# owl-digital-2.net
KiCad netlist of a schematic drawn in EAGLE
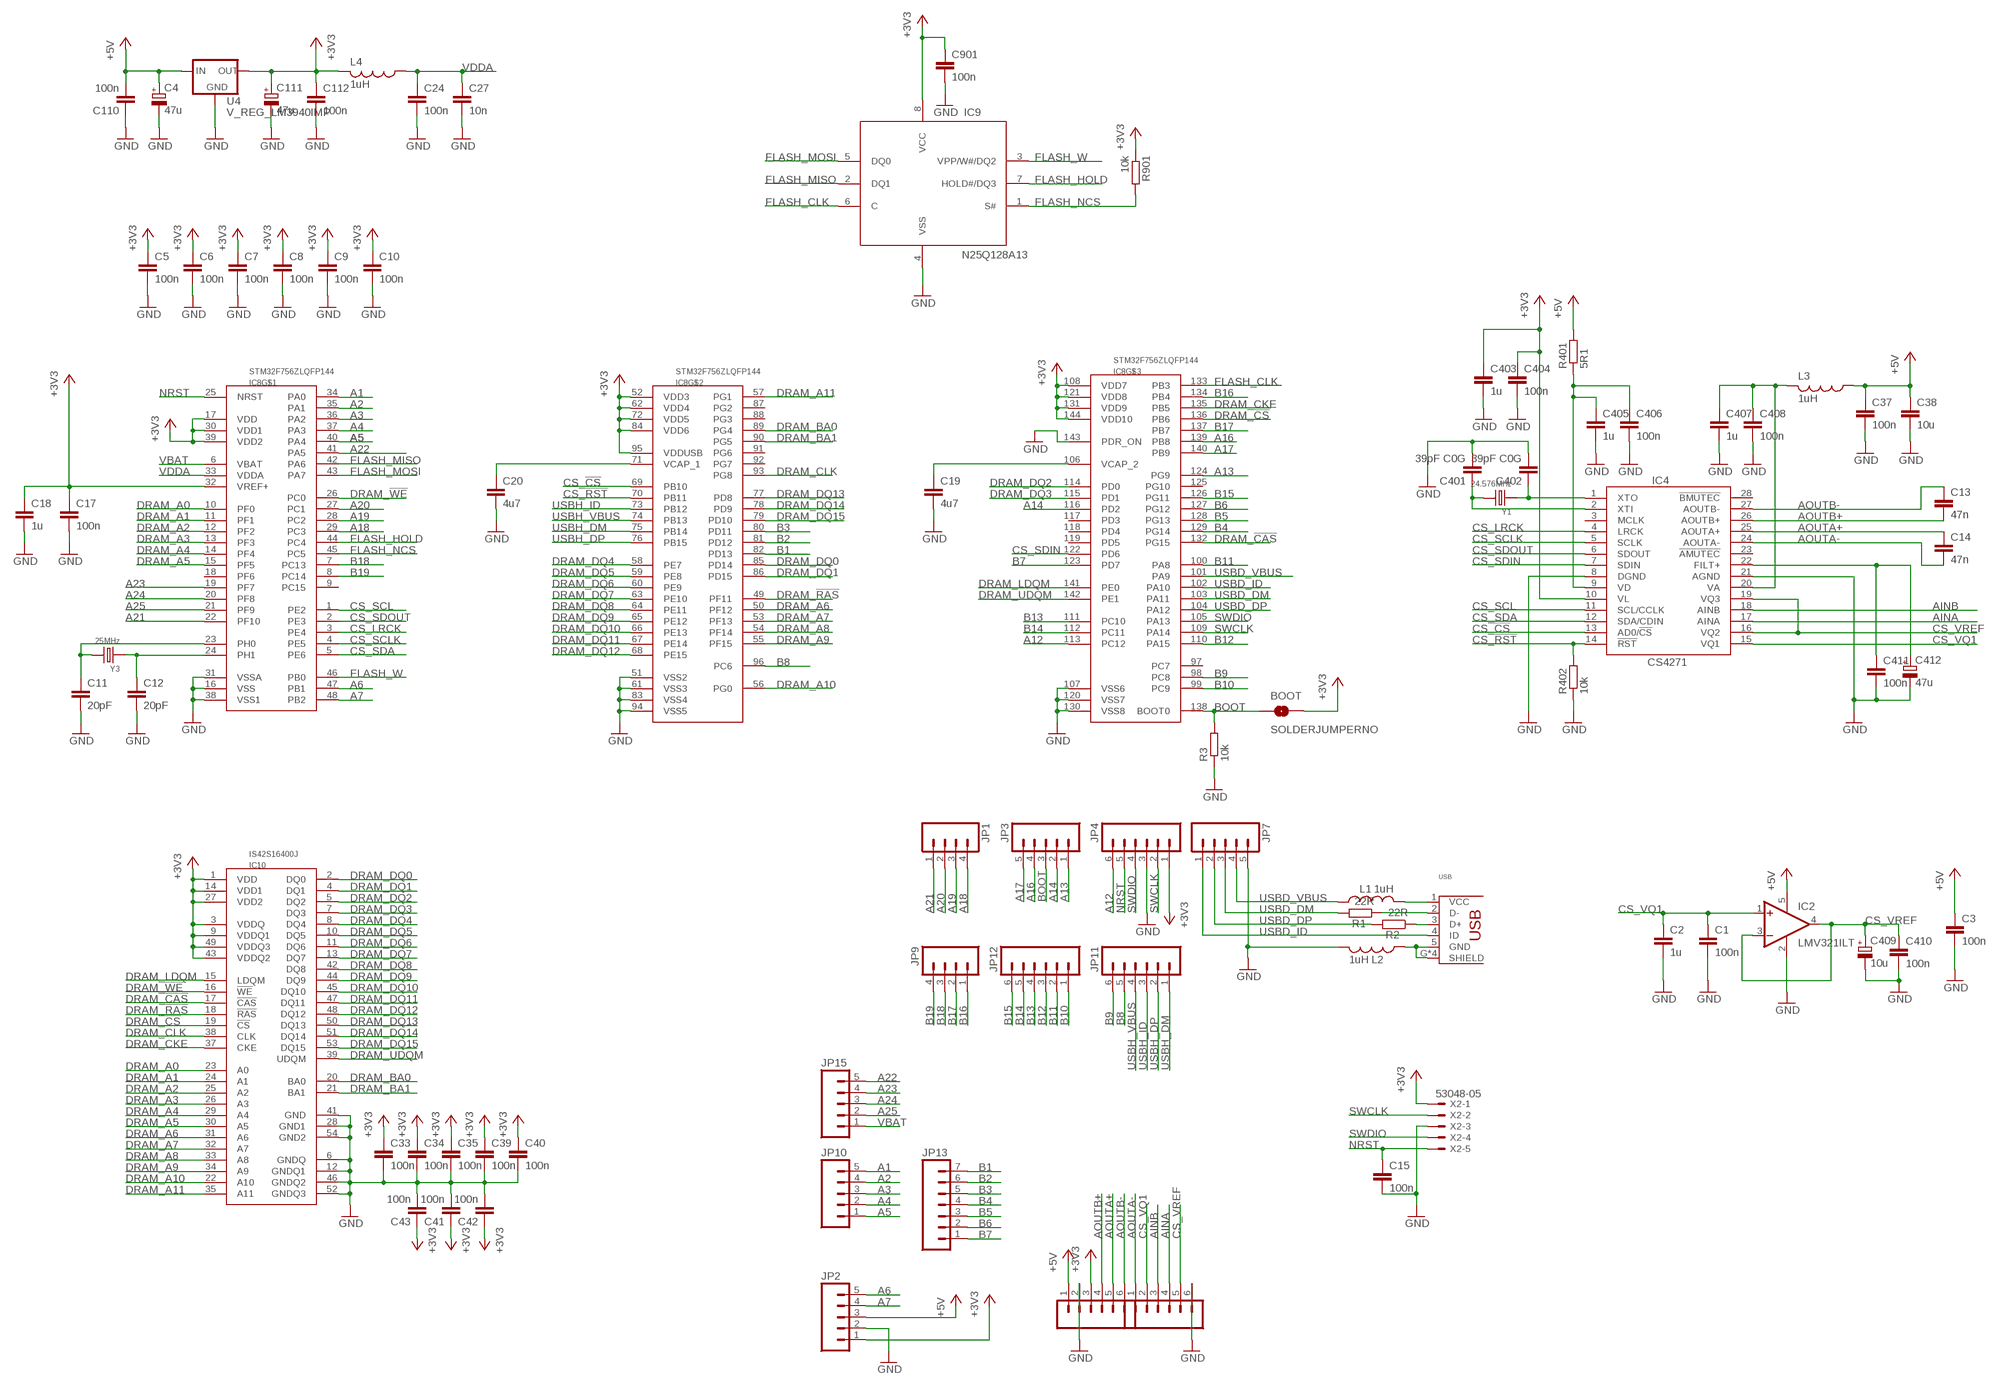
[diagram p0: schematic, sheet 1]

(export (version "E")
  (design (tool "Eeschema 10.0.6"))
  (components
    (comp (ref "BOOT")
      (value "SOLDERJUMPERNO")
      (footprint "eagle-import:SJ_2S-NO")
      (libsource (lib "eagle-import") (part "SOLDERJUMPERNO"))
    )
    (comp (ref "C1")
      (value "100n")
      (footprint "eagle-import:C0603")
      (libsource (lib "eagle-import") (part "C-EUC0603"))
    )
    (comp (ref "C2")
      (value "1u")
      (footprint "eagle-import:C0603")
      (libsource (lib "eagle-import") (part "C-EUC0603"))
    )
    (comp (ref "C3")
      (value "100n")
      (footprint "eagle-import:C0603")
      (libsource (lib "eagle-import") (part "C-EUC0603"))
    )
    (comp (ref "C4")
      (value "47u")
      (footprint "eagle-import:CPOL-5")
      (libsource (lib "eagle-import") (part "CPOL-EU153CLV-0505"))
    )
    (comp (ref "C5")
      (value "100n")
      (footprint "eagle-import:C0603")
      (libsource (lib "eagle-import") (part "C-EUC0603"))
    )
    (comp (ref "C6")
      (value "100n")
      (footprint "eagle-import:C0603")
      (libsource (lib "eagle-import") (part "C-EUC0603"))
    )
    (comp (ref "C7")
      (value "100n")
      (footprint "eagle-import:C0603")
      (libsource (lib "eagle-import") (part "C-EUC0603"))
    )
    (comp (ref "C8")
      (value "100n")
      (footprint "eagle-import:C0603")
      (libsource (lib "eagle-import") (part "C-EUC0603"))
    )
    (comp (ref "C9")
      (value "100n")
      (footprint "eagle-import:C0603")
      (libsource (lib "eagle-import") (part "C-EUC0603"))
    )
    (comp (ref "C10")
      (value "100n")
      (footprint "eagle-import:C0603")
      (libsource (lib "eagle-import") (part "C-EUC0603"))
    )
    (comp (ref "C11")
      (value "20pF")
      (footprint "eagle-import:C0603")
      (libsource (lib "eagle-import") (part "C-EUC0603"))
    )
    (comp (ref "C12")
      (value "20pF")
      (footprint "eagle-import:C0603")
      (libsource (lib "eagle-import") (part "C-EUC0603"))
    )
    (comp (ref "C13")
      (value "47n")
      (footprint "eagle-import:C0603")
      (libsource (lib "eagle-import") (part "C-EUC0603"))
    )
    (comp (ref "C14")
      (value "47n")
      (footprint "eagle-import:C0603")
      (libsource (lib "eagle-import") (part "C-EUC0603"))
    )
    (comp (ref "C15")
      (value "100n")
      (footprint "eagle-import:C0603")
      (libsource (lib "eagle-import") (part "C-EUC0603"))
    )
    (comp (ref "C17")
      (value "100n")
      (footprint "eagle-import:C0603")
      (libsource (lib "eagle-import") (part "C-EUC0603"))
    )
    (comp (ref "C18")
      (value "1u")
      (footprint "eagle-import:C0603")
      (libsource (lib "eagle-import") (part "C-EUC0603"))
    )
    (comp (ref "C19")
      (value "4u7")
      (footprint "eagle-import:C0603")
      (libsource (lib "eagle-import") (part "C-EUC0603"))
    )
    (comp (ref "C20")
      (value "4u7")
      (footprint "eagle-import:C0603")
      (libsource (lib "eagle-import") (part "C-EUC0603"))
    )
    (comp (ref "C24")
      (value "100n")
      (footprint "eagle-import:C0603")
      (libsource (lib "eagle-import") (part "C-EUC0603"))
    )
    (comp (ref "C27")
      (value "10n")
      (footprint "eagle-import:C0603")
      (libsource (lib "eagle-import") (part "C-EUC0603"))
    )
    (comp (ref "C33")
      (value "100n")
      (footprint "eagle-import:C0603")
      (libsource (lib "eagle-import") (part "C-EUC0603"))
    )
    (comp (ref "C34")
      (value "100n")
      (footprint "eagle-import:C0603")
      (libsource (lib "eagle-import") (part "C-EUC0603"))
    )
    (comp (ref "C35")
      (value "100n")
      (footprint "eagle-import:C0603")
      (libsource (lib "eagle-import") (part "C-EUC0603"))
    )
    (comp (ref "C37")
      (value "100n")
      (footprint "eagle-import:C0603")
      (libsource (lib "eagle-import") (part "C-EUC0603"))
    )
    (comp (ref "C38")
      (value "10u")
      (footprint "eagle-import:C1206")
      (libsource (lib "eagle-import") (part "C-EUC1206"))
    )
    (comp (ref "C39")
      (value "100n")
      (footprint "eagle-import:C0603")
      (libsource (lib "eagle-import") (part "C-EUC0603"))
    )
    (comp (ref "C40")
      (value "100n")
      (footprint "eagle-import:C0603")
      (libsource (lib "eagle-import") (part "C-EUC0603"))
    )
    (comp (ref "C41")
      (value "100n")
      (footprint "eagle-import:C0603")
      (libsource (lib "eagle-import") (part "C-EUC0603"))
    )
    (comp (ref "C42")
      (value "100n")
      (footprint "eagle-import:C0603")
      (libsource (lib "eagle-import") (part "C-EUC0603"))
    )
    (comp (ref "C43")
      (value "100n")
      (footprint "eagle-import:C0603")
      (libsource (lib "eagle-import") (part "C-EUC0603"))
    )
    (comp (ref "C110")
      (value "100n")
      (footprint "eagle-import:C0603")
      (libsource (lib "eagle-import") (part "C-EUC0603"))
    )
    (comp (ref "C111")
      (value "47u")
      (footprint "eagle-import:CPOL-5")
      (libsource (lib "eagle-import") (part "CPOL-EU153CLV-0505"))
    )
    (comp (ref "C112")
      (value "100n")
      (footprint "eagle-import:C0603")
      (libsource (lib "eagle-import") (part "C-EUC0603"))
    )
    (comp (ref "C401")
      (value "39pF C0G")
      (footprint "eagle-import:C0603")
      (libsource (lib "eagle-import") (part "C-EUC0603"))
    )
    (comp (ref "C402")
      (value "39pF C0G")
      (footprint "eagle-import:C0603")
      (libsource (lib "eagle-import") (part "C-EUC0603"))
    )
    (comp (ref "C403")
      (value "1u")
      (footprint "eagle-import:C0603")
      (libsource (lib "eagle-import") (part "C-EUC0603"))
    )
    (comp (ref "C404")
      (value "100n")
      (footprint "eagle-import:C0603")
      (libsource (lib "eagle-import") (part "C-EUC0603"))
    )
    (comp (ref "C405")
      (value "1u")
      (footprint "eagle-import:C0603")
      (libsource (lib "eagle-import") (part "C-EUC0603"))
    )
    (comp (ref "C406")
      (value "100n")
      (footprint "eagle-import:C0603")
      (libsource (lib "eagle-import") (part "C-EUC0603"))
    )
    (comp (ref "C407")
      (value "1u")
      (footprint "eagle-import:C0603")
      (libsource (lib "eagle-import") (part "C-EUC0603"))
    )
    (comp (ref "C408")
      (value "100n")
      (footprint "eagle-import:C0603")
      (libsource (lib "eagle-import") (part "C-EUC0603"))
    )
    (comp (ref "C409")
      (value "10u")
      (footprint "eagle-import:CPOL-5")
      (libsource (lib "eagle-import") (part "CPOL-EU153CLV-0505"))
    )
    (comp (ref "C410")
      (value "100n")
      (footprint "eagle-import:C0603")
      (libsource (lib "eagle-import") (part "C-EUC0603"))
    )
    (comp (ref "C411")
      (value "100n")
      (footprint "eagle-import:C0603")
      (libsource (lib "eagle-import") (part "C-EUC0603"))
    )
    (comp (ref "C412")
      (value "47u")
      (footprint "eagle-import:CPOL-5")
      (libsource (lib "eagle-import") (part "CPOL-EU153CLV-0505"))
    )
    (comp (ref "C901")
      (value "100n")
      (footprint "eagle-import:C0603")
      (libsource (lib "eagle-import") (part "C-EUC0603"))
    )
    (comp (ref "IC2")
      (value "LMV321ILT")
      (footprint "eagle-import:SOT23-5")
      (libsource (lib "eagle-import") (part "LM321?MF"))
    )
    (comp (ref "IC4")
      (value "CS4271")
      (footprint "eagle-import:TSSOP28-0.65-9.7X4.4MM")
      (libsource (lib "eagle-import") (part "CS4271"))
    )
    (comp (ref "IC8")
      (value "STM32F756ZLQFP144")
      (footprint "eagle-import:QFP50P2200X2200X160-144N")
      (fields (field (name "OC_FARNELL") "2484975"))
      (libsource (lib "eagle-import") (part "STM32F756ZLQFP144"))
    )
    (comp (ref "IC9")
      (value "N25Q128A13")
      (footprint "eagle-import:SO8W")
      (libsource (lib "eagle-import") (part "N25Q128A13"))
    )
    (comp (ref "IC10")
      (value "IS42S16400J")
      (footprint "eagle-import:TSOP54-400")
      (libsource (lib "eagle-import") (part "IS42S16400J"))
    )
    (comp (ref "JP1")
      (value "M04PTH")
      (footprint "eagle-import:1X04")
      (libsource (lib "eagle-import") (part "M04PTH"))
    )
    (comp (ref "JP2")
      (value "M05PTH")
      (footprint "eagle-import:1X05")
      (libsource (lib "eagle-import") (part "M05PTH"))
    )
    (comp (ref "JP3")
      (value "M05PTH")
      (footprint "eagle-import:1X05")
      (libsource (lib "eagle-import") (part "M05PTH"))
    )
    (comp (ref "JP4")
      (value "M06SIP")
      (footprint "eagle-import:1X06")
      (libsource (lib "eagle-import") (part "M06SIP"))
    )
    (comp (ref "JP5")
      (value "M06SIP")
      (footprint "eagle-import:1X06")
      (libsource (lib "eagle-import") (part "M06SIP"))
    )
    (comp (ref "JP6")
      (value "M06SIP")
      (footprint "eagle-import:1X06")
      (libsource (lib "eagle-import") (part "M06SIP"))
    )
    (comp (ref "JP7")
      (value "M05PTH")
      (footprint "eagle-import:1X05")
      (libsource (lib "eagle-import") (part "M05PTH"))
    )
    (comp (ref "JP9")
      (value "M04PTH")
      (footprint "eagle-import:1X04")
      (libsource (lib "eagle-import") (part "M04PTH"))
    )
    (comp (ref "JP10")
      (value "M05PTH")
      (footprint "eagle-import:1X05")
      (libsource (lib "eagle-import") (part "M05PTH"))
    )
    (comp (ref "JP11")
      (value "M06SIP")
      (footprint "eagle-import:1X06")
      (libsource (lib "eagle-import") (part "M06SIP"))
    )
    (comp (ref "JP12")
      (value "M06SIP")
      (footprint "eagle-import:1X06")
      (libsource (lib "eagle-import") (part "M06SIP"))
    )
    (comp (ref "JP13")
      (value "M07")
      (footprint "eagle-import:1X07")
      (libsource (lib "eagle-import") (part "M07"))
    )
    (comp (ref "JP15")
      (value "M05PTH")
      (footprint "eagle-import:1X05")
      (libsource (lib "eagle-import") (part "M05PTH"))
    )
    (comp (ref "L1")
      (value "1uH")
      (footprint "eagle-import:0603")
      (libsource (lib "eagle-import") (part "INDUCTOR"))
    )
    (comp (ref "L2")
      (value "1uH")
      (footprint "eagle-import:0603")
      (libsource (lib "eagle-import") (part "INDUCTOR"))
    )
    (comp (ref "L3")
      (value "1uH")
      (footprint "eagle-import:0603")
      (libsource (lib "eagle-import") (part "INDUCTOR"))
    )
    (comp (ref "L4")
      (value "1uH")
      (footprint "eagle-import:0603")
      (libsource (lib "eagle-import") (part "INDUCTOR"))
    )
    (comp (ref "R1")
      (value "22R")
      (footprint "eagle-import:0603")
      (libsource (lib "eagle-import") (part "R-EU_0603"))
    )
    (comp (ref "R2")
      (value "22R")
      (footprint "eagle-import:0603")
      (libsource (lib "eagle-import") (part "R-EU_0603"))
    )
    (comp (ref "R3")
      (value "10k")
      (footprint "eagle-import:0603")
      (libsource (lib "eagle-import") (part "R-EU_0603"))
    )
    (comp (ref "R401")
      (value "5R1")
      (footprint "eagle-import:0603")
      (libsource (lib "eagle-import") (part "R-EU_0603"))
    )
    (comp (ref "R402")
      (value "10k")
      (footprint "eagle-import:0603")
      (libsource (lib "eagle-import") (part "R-EU_0603"))
    )
    (comp (ref "R901")
      (value "10k")
      (footprint "eagle-import:0603")
      (libsource (lib "eagle-import") (part "R-EU_0603"))
    )
    (comp (ref "U4")
      (value "V_REG_LM3940IMP")
      (footprint "eagle-import:SOT223")
      (libsource (lib "eagle-import") (part "V_REG_LM3940IMP"))
    )
    (comp (ref "USB")
      (value "USB_HRS_ZX62-B-5PA(11)MICRO.B")
      (footprint "eagle-import:HRS_ZX62RD-AB-5P8")
      (libsource (lib "eagle-import") (part "USB_HRS_ZX62-B-5PA(11)MICRO.B"))
    )
    (comp (ref "X2")
      (value "53048-05")
      (footprint "eagle-import:53048-05")
      (fields (field (name "MF") "MOLEX") (field (name "MPN") "53048-0510"))
      (libsource (lib "eagle-import") (part "53?-05048"))
    )
    (comp (ref "Y1")
      (value "24.576MHz")
      (footprint "eagle-import:X2-SMD-5.0X3.2X1.3MM")
      (fields (field (name "MPN") "5032/2P"))
      (libsource (lib "eagle-import") (part "SMD-CRYSTAL-8MHZ-20PF-20PPM(2P-5.0X3.2MM)"))
    )
    (comp (ref "Y3")
      (value "25MHz")
      (footprint "eagle-import:X2-SMD-5.0X3.2X1.3MM")
      (fields (field (name "MPN") "5032/2P"))
      (libsource (lib "eagle-import") (part "SMD-CRYSTAL-8MHZ-20PF-20PPM(2P-5.0X3.2MM)"))
    )
  )
  (nets
    (net (code "1") (name "+3V3") (class "Default")
      (node (ref "BOOT") (pin "2") (pinfunction "2_2") (pintype "passive"))
      (node (ref "C10") (pin "1") (pinfunction "1_1") (pintype "passive"))
      (node (ref "C111") (pin "+") (pinfunction "+_+") (pintype "passive"))
      (node (ref "C112") (pin "1") (pinfunction "1_1") (pintype "passive"))
      (node (ref "C17") (pin "1") (pinfunction "1_1") (pintype "passive"))
      (node (ref "C18") (pin "1") (pinfunction "1_1") (pintype "passive"))
      (node (ref "C33") (pin "1") (pinfunction "1_1") (pintype "passive"))
      (node (ref "C34") (pin "1") (pinfunction "1_1") (pintype "passive"))
      (node (ref "C35") (pin "1") (pinfunction "1_1") (pintype "passive"))
      (node (ref "C39") (pin "1") (pinfunction "1_1") (pintype "passive"))
      (node (ref "C40") (pin "1") (pinfunction "1_1") (pintype "passive"))
      (node (ref "C403") (pin "1") (pinfunction "1_1") (pintype "passive"))
      (node (ref "C404") (pin "1") (pinfunction "1_1") (pintype "passive"))
      (node (ref "C41") (pin "1") (pinfunction "1_1") (pintype "passive"))
      (node (ref "C42") (pin "1") (pinfunction "1_1") (pintype "passive"))
      (node (ref "C43") (pin "1") (pinfunction "1_1") (pintype "passive"))
      (node (ref "C5") (pin "1") (pinfunction "1_1") (pintype "passive"))
      (node (ref "C6") (pin "1") (pinfunction "1_1") (pintype "passive"))
      (node (ref "C7") (pin "1") (pinfunction "1_1") (pintype "passive"))
      (node (ref "C8") (pin "1") (pinfunction "1_1") (pintype "passive"))
      (node (ref "C9") (pin "1") (pinfunction "1_1") (pintype "passive"))
      (node (ref "C901") (pin "1") (pinfunction "1_1") (pintype "passive"))
      (node (ref "IC10") (pin "1") (pinfunction "VDD_1") (pintype "bidirectional"))
      (node (ref "IC10") (pin "14") (pinfunction "VDD1_14") (pintype "bidirectional"))
      (node (ref "IC10") (pin "27") (pinfunction "VDD2_27") (pintype "bidirectional"))
      (node (ref "IC10") (pin "3") (pinfunction "VDDQ_3") (pintype "bidirectional"))
      (node (ref "IC10") (pin "43") (pinfunction "VDDQ2_43") (pintype "bidirectional"))
      (node (ref "IC10") (pin "49") (pinfunction "VDDQ3_49") (pintype "bidirectional"))
      (node (ref "IC10") (pin "9") (pinfunction "VDDQ1_9") (pintype "bidirectional"))
      (node (ref "IC4") (pin "10") (pinfunction "VL_10") (pintype "bidirectional"))
      (node (ref "IC8") (pin "108") (pinfunction "VDD7_108") (pintype "bidirectional"))
      (node (ref "IC8") (pin "121") (pinfunction "VDD8_121") (pintype "bidirectional"))
      (node (ref "IC8") (pin "131") (pinfunction "VDD9_131") (pintype "bidirectional"))
      (node (ref "IC8") (pin "144") (pinfunction "VDD10_144") (pintype "bidirectional"))
      (node (ref "IC8") (pin "17") (pinfunction "VDD_17") (pintype "bidirectional"))
      (node (ref "IC8") (pin "30") (pinfunction "VDD1_30") (pintype "bidirectional"))
      (node (ref "IC8") (pin "32") (pinfunction "VREF+_32") (pintype "bidirectional"))
      (node (ref "IC8") (pin "39") (pinfunction "VDD2_39") (pintype "bidirectional"))
      (node (ref "IC8") (pin "52") (pinfunction "VDD3_52") (pintype "bidirectional"))
      (node (ref "IC8") (pin "62") (pinfunction "VDD4_62") (pintype "bidirectional"))
      (node (ref "IC8") (pin "72") (pinfunction "VDD5_72") (pintype "bidirectional"))
      (node (ref "IC8") (pin "84") (pinfunction "VDD6_84") (pintype "bidirectional"))
      (node (ref "IC8") (pin "95") (pinfunction "VDDUSB_95") (pintype "bidirectional"))
      (node (ref "IC9") (pin "8") (pinfunction "VCC_8") (pintype "bidirectional"))
      (node (ref "JP2") (pin "1") (pinfunction "1_1") (pintype "passive"))
      (node (ref "JP4") (pin "1") (pinfunction "1_1") (pintype "passive"))
      (node (ref "JP5") (pin "3") (pinfunction "3_3") (pintype "passive"))
      (node (ref "L4") (pin "2") (pinfunction "2_2") (pintype "passive"))
      (node (ref "R901") (pin "1") (pinfunction "1_1") (pintype "passive"))
      (node (ref "U4") (pin "3") (pinfunction "OUT_3") (pintype "output"))
      (node (ref "X2") (pin "1") (pinfunction "S_1") (pintype "passive"))
    )
    (net (code "2") (name "+5V") (class "Default")
      (node (ref "C110") (pin "2") (pinfunction "2_2") (pintype "passive"))
      (node (ref "C3") (pin "1") (pinfunction "1_1") (pintype "passive"))
      (node (ref "C37") (pin "1") (pinfunction "1_1") (pintype "passive"))
      (node (ref "C38") (pin "1") (pinfunction "1_1") (pintype "passive"))
      (node (ref "C4") (pin "+") (pinfunction "+_+") (pintype "passive"))
      (node (ref "IC2") (pin "5") (pinfunction "V+_5") (pintype "power_in"))
      (node (ref "JP2") (pin "3") (pinfunction "3_3") (pintype "passive"))
      (node (ref "JP5") (pin "1") (pinfunction "1_1") (pintype "passive"))
      (node (ref "L3") (pin "1") (pinfunction "1_1") (pintype "passive"))
      (node (ref "R401") (pin "2") (pinfunction "2_2") (pintype "passive"))
      (node (ref "U4") (pin "1") (pinfunction "IN_1") (pintype "input"))
    )
    (net (code "3") (name "/A1") (class "Default")
      (node (ref "IC8") (pin "34") (pinfunction "PA0_34") (pintype "bidirectional"))
      (node (ref "JP10") (pin "5") (pinfunction "5_5") (pintype "passive"))
    )
    (net (code "4") (name "/A2") (class "Default")
      (node (ref "IC8") (pin "35") (pinfunction "PA1_35") (pintype "bidirectional"))
      (node (ref "JP10") (pin "4") (pinfunction "4_4") (pintype "passive"))
    )
    (net (code "5") (name "/A3") (class "Default")
      (node (ref "IC8") (pin "36") (pinfunction "PA2_36") (pintype "bidirectional"))
      (node (ref "JP10") (pin "3") (pinfunction "3_3") (pintype "passive"))
    )
    (net (code "6") (name "/A4") (class "Default")
      (node (ref "IC8") (pin "37") (pinfunction "PA3_37") (pintype "bidirectional"))
      (node (ref "JP10") (pin "2") (pinfunction "2_2") (pintype "passive"))
    )
    (net (code "7") (name "/A5") (class "Default")
      (node (ref "IC8") (pin "40") (pinfunction "PA4_40") (pintype "bidirectional"))
      (node (ref "JP10") (pin "1") (pinfunction "1_1") (pintype "passive"))
    )
    (net (code "8") (name "/A6") (class "Default")
      (node (ref "IC8") (pin "47") (pinfunction "PB1_47") (pintype "bidirectional"))
      (node (ref "JP2") (pin "5") (pinfunction "5_5") (pintype "passive"))
    )
    (net (code "9") (name "/A7") (class "Default")
      (node (ref "IC8") (pin "48") (pinfunction "PB2_48") (pintype "bidirectional"))
      (node (ref "JP2") (pin "4") (pinfunction "4_4") (pintype "passive"))
    )
    (net (code "10") (name "/A12") (class "Default")
      (node (ref "IC8") (pin "113") (pinfunction "PC12_113") (pintype "bidirectional"))
      (node (ref "JP4") (pin "6") (pinfunction "6_6") (pintype "passive"))
    )
    (net (code "11") (name "/A13") (class "Default")
      (node (ref "IC8") (pin "124") (pinfunction "PG9_124") (pintype "bidirectional"))
      (node (ref "JP3") (pin "1") (pinfunction "1_1") (pintype "passive"))
    )
    (net (code "12") (name "/A14") (class "Default")
      (node (ref "IC8") (pin "116") (pinfunction "PD2_116") (pintype "bidirectional"))
      (node (ref "JP3") (pin "2") (pinfunction "2_2") (pintype "passive"))
    )
    (net (code "13") (name "/A16") (class "Default")
      (node (ref "IC8") (pin "139") (pinfunction "PB8_139") (pintype "bidirectional"))
      (node (ref "JP3") (pin "4") (pinfunction "4_4") (pintype "passive"))
    )
    (net (code "14") (name "/A17") (class "Default")
      (node (ref "IC8") (pin "140") (pinfunction "PB9_140") (pintype "bidirectional"))
      (node (ref "JP3") (pin "5") (pinfunction "5_5") (pintype "passive"))
    )
    (net (code "15") (name "/A18") (class "Default")
      (node (ref "IC8") (pin "29") (pinfunction "PC3_29") (pintype "bidirectional"))
      (node (ref "JP1") (pin "4") (pinfunction "4_4") (pintype "passive"))
    )
    (net (code "16") (name "/A19") (class "Default")
      (node (ref "IC8") (pin "28") (pinfunction "PC2_28") (pintype "bidirectional"))
      (node (ref "JP1") (pin "3") (pinfunction "3_3") (pintype "passive"))
    )
    (net (code "17") (name "/A20") (class "Default")
      (node (ref "IC8") (pin "27") (pinfunction "PC1_27") (pintype "bidirectional"))
      (node (ref "JP1") (pin "2") (pinfunction "2_2") (pintype "passive"))
    )
    (net (code "18") (name "/A21") (class "Default")
      (node (ref "IC8") (pin "22") (pinfunction "PF10_22") (pintype "bidirectional"))
      (node (ref "JP1") (pin "1") (pinfunction "1_1") (pintype "passive"))
    )
    (net (code "19") (name "/A22") (class "Default")
      (node (ref "IC8") (pin "41") (pinfunction "PA5_41") (pintype "bidirectional"))
      (node (ref "JP15") (pin "5") (pinfunction "5_5") (pintype "passive"))
    )
    (net (code "20") (name "/A23") (class "Default")
      (node (ref "IC8") (pin "19") (pinfunction "PF7_19") (pintype "bidirectional"))
      (node (ref "JP15") (pin "4") (pinfunction "4_4") (pintype "passive"))
    )
    (net (code "21") (name "/A24") (class "Default")
      (node (ref "IC8") (pin "20") (pinfunction "PF8_20") (pintype "bidirectional"))
      (node (ref "JP15") (pin "3") (pinfunction "3_3") (pintype "passive"))
    )
    (net (code "22") (name "/A25") (class "Default")
      (node (ref "IC8") (pin "21") (pinfunction "PF9_21") (pintype "bidirectional"))
      (node (ref "JP15") (pin "2") (pinfunction "2_2") (pintype "passive"))
    )
    (net (code "23") (name "/AINA") (class "Default")
      (node (ref "IC4") (pin "17") (pinfunction "AINA_17") (pintype "bidirectional"))
      (node (ref "JP6") (pin "4") (pinfunction "4_4") (pintype "passive"))
    )
    (net (code "24") (name "/AINB") (class "Default")
      (node (ref "IC4") (pin "18") (pinfunction "AINB_18") (pintype "bidirectional"))
      (node (ref "JP6") (pin "3") (pinfunction "3_3") (pintype "passive"))
    )
    (net (code "25") (name "/AOUTA+") (class "Default")
      (node (ref "C14") (pin "1") (pinfunction "1_1") (pintype "passive"))
      (node (ref "IC4") (pin "25") (pinfunction "AOUTA+_25") (pintype "bidirectional"))
      (node (ref "JP5") (pin "5") (pinfunction "5_5") (pintype "passive"))
    )
    (net (code "26") (name "/AOUTA-") (class "Default")
      (node (ref "C14") (pin "2") (pinfunction "2_2") (pintype "passive"))
      (node (ref "IC4") (pin "24") (pinfunction "AOUTA-_24") (pintype "bidirectional"))
      (node (ref "JP6") (pin "1") (pinfunction "1_1") (pintype "passive"))
    )
    (net (code "27") (name "/AOUTB+") (class "Default")
      (node (ref "C13") (pin "2") (pinfunction "2_2") (pintype "passive"))
      (node (ref "IC4") (pin "26") (pinfunction "AOUTB+_26") (pintype "bidirectional"))
      (node (ref "JP5") (pin "4") (pinfunction "4_4") (pintype "passive"))
    )
    (net (code "28") (name "/AOUTB-") (class "Default")
      (node (ref "C13") (pin "1") (pinfunction "1_1") (pintype "passive"))
      (node (ref "IC4") (pin "27") (pinfunction "AOUTB-_27") (pintype "bidirectional"))
      (node (ref "JP5") (pin "6") (pinfunction "6_6") (pintype "passive"))
    )
    (net (code "29") (name "/B1") (class "Default")
      (node (ref "IC8") (pin "82") (pinfunction "PD13_82") (pintype "bidirectional"))
      (node (ref "JP13") (pin "7") (pinfunction "7_7") (pintype "passive"))
    )
    (net (code "30") (name "/B2") (class "Default")
      (node (ref "IC8") (pin "81") (pinfunction "PD12_81") (pintype "bidirectional"))
      (node (ref "JP13") (pin "6") (pinfunction "6_6") (pintype "passive"))
    )
    (net (code "31") (name "/B3") (class "Default")
      (node (ref "IC8") (pin "80") (pinfunction "PD11_80") (pintype "bidirectional"))
      (node (ref "JP13") (pin "5") (pinfunction "5_5") (pintype "passive"))
    )
    (net (code "32") (name "/B4") (class "Default")
      (node (ref "IC8") (pin "129") (pinfunction "PG14_129") (pintype "bidirectional"))
      (node (ref "JP13") (pin "4") (pinfunction "4_4") (pintype "passive"))
    )
    (net (code "33") (name "/B5") (class "Default")
      (node (ref "IC8") (pin "128") (pinfunction "PG13_128") (pintype "bidirectional"))
      (node (ref "JP13") (pin "3") (pinfunction "3_3") (pintype "passive"))
    )
    (net (code "34") (name "/B6") (class "Default")
      (node (ref "IC8") (pin "127") (pinfunction "PG12_127") (pintype "bidirectional"))
      (node (ref "JP13") (pin "2") (pinfunction "2_2") (pintype "passive"))
    )
    (net (code "35") (name "/B7") (class "Default")
      (node (ref "IC8") (pin "123") (pinfunction "PD7_123") (pintype "bidirectional"))
      (node (ref "JP13") (pin "1") (pinfunction "1_1") (pintype "passive"))
    )
    (net (code "36") (name "/B8") (class "Default")
      (node (ref "IC8") (pin "96") (pinfunction "PC6_96") (pintype "bidirectional"))
      (node (ref "JP11") (pin "5") (pinfunction "5_5") (pintype "passive"))
    )
    (net (code "37") (name "/B9") (class "Default")
      (node (ref "IC8") (pin "98") (pinfunction "PC8_98") (pintype "bidirectional"))
      (node (ref "JP11") (pin "6") (pinfunction "6_6") (pintype "passive"))
    )
    (net (code "38") (name "/B10") (class "Default")
      (node (ref "IC8") (pin "99") (pinfunction "PC9_99") (pintype "bidirectional"))
      (node (ref "JP12") (pin "1") (pinfunction "1_1") (pintype "passive"))
    )
    (net (code "39") (name "/B11") (class "Default")
      (node (ref "IC8") (pin "100") (pinfunction "PA8_100") (pintype "bidirectional"))
      (node (ref "JP12") (pin "2") (pinfunction "2_2") (pintype "passive"))
    )
    (net (code "40") (name "/B12") (class "Default")
      (node (ref "IC8") (pin "110") (pinfunction "PA15_110") (pintype "bidirectional"))
      (node (ref "JP12") (pin "3") (pinfunction "3_3") (pintype "passive"))
    )
    (net (code "41") (name "/B13") (class "Default")
      (node (ref "IC8") (pin "111") (pinfunction "PC10_111") (pintype "bidirectional"))
      (node (ref "JP12") (pin "4") (pinfunction "4_4") (pintype "passive"))
    )
    (net (code "42") (name "/B14") (class "Default")
      (node (ref "IC8") (pin "112") (pinfunction "PC11_112") (pintype "bidirectional"))
      (node (ref "JP12") (pin "5") (pinfunction "5_5") (pintype "passive"))
    )
    (net (code "43") (name "/B15") (class "Default")
      (node (ref "IC8") (pin "126") (pinfunction "PG11_126") (pintype "bidirectional"))
      (node (ref "JP12") (pin "6") (pinfunction "6_6") (pintype "passive"))
    )
    (net (code "44") (name "/B16") (class "Default")
      (node (ref "IC8") (pin "134") (pinfunction "PB4_134") (pintype "bidirectional"))
      (node (ref "JP9") (pin "1") (pinfunction "1_1") (pintype "passive"))
    )
    (net (code "45") (name "/B17") (class "Default")
      (node (ref "IC8") (pin "137") (pinfunction "PB7_137") (pintype "bidirectional"))
      (node (ref "JP9") (pin "2") (pinfunction "2_2") (pintype "passive"))
    )
    (net (code "46") (name "/B18") (class "Default")
      (node (ref "IC8") (pin "7") (pinfunction "PC13_7") (pintype "bidirectional"))
      (node (ref "JP9") (pin "3") (pinfunction "3_3") (pintype "passive"))
    )
    (net (code "47") (name "/B19") (class "Default")
      (node (ref "IC8") (pin "8") (pinfunction "PC14_8") (pintype "bidirectional"))
      (node (ref "JP9") (pin "4") (pinfunction "4_4") (pintype "passive"))
    )
    (net (code "48") (name "/BOOT") (class "Default")
      (node (ref "BOOT") (pin "1") (pinfunction "1_1") (pintype "passive"))
      (node (ref "IC8") (pin "138") (pinfunction "BOOT0_138") (pintype "bidirectional"))
      (node (ref "JP3") (pin "3") (pinfunction "3_3") (pintype "passive"))
      (node (ref "R3") (pin "2") (pinfunction "2_2") (pintype "passive"))
    )
    (net (code "49") (name "/CS_LRCK") (class "Default")
      (node (ref "IC4") (pin "4") (pinfunction "LRCK_4") (pintype "bidirectional"))
      (node (ref "IC8") (pin "3") (pinfunction "PE4_3") (pintype "bidirectional"))
    )
    (net (code "50") (name "/CS_SCL") (class "Default")
      (node (ref "IC4") (pin "11") (pinfunction "SCL/CCLK_11") (pintype "bidirectional"))
      (node (ref "IC8") (pin "1") (pinfunction "PE2_1") (pintype "bidirectional"))
    )
    (net (code "51") (name "/CS_SCLK") (class "Default")
      (node (ref "IC4") (pin "5") (pinfunction "SCLK_5") (pintype "bidirectional"))
      (node (ref "IC8") (pin "4") (pinfunction "PE5_4") (pintype "bidirectional"))
    )
    (net (code "52") (name "/CS_SDA") (class "Default")
      (node (ref "IC4") (pin "12") (pinfunction "SDA/CDIN_12") (pintype "bidirectional"))
      (node (ref "IC8") (pin "5") (pinfunction "PE6_5") (pintype "bidirectional"))
    )
    (net (code "53") (name "/CS_SDIN") (class "Default")
      (node (ref "IC4") (pin "7") (pinfunction "SDIN_7") (pintype "bidirectional"))
      (node (ref "IC8") (pin "122") (pinfunction "PD6_122") (pintype "bidirectional"))
    )
    (net (code "54") (name "/CS_SDOUT") (class "Default")
      (node (ref "IC4") (pin "6") (pinfunction "SDOUT_6") (pintype "bidirectional"))
      (node (ref "IC8") (pin "2") (pinfunction "PE3_2") (pintype "bidirectional"))
    )
    (net (code "55") (name "/CS_VQ1") (class "Default")
      (node (ref "C1") (pin "1") (pinfunction "1_1") (pintype "passive"))
      (node (ref "C2") (pin "1") (pinfunction "1_1") (pintype "passive"))
      (node (ref "IC2") (pin "1") (pinfunction "+IN_1") (pintype "input"))
      (node (ref "IC4") (pin "15") (pinfunction "VQ1_15") (pintype "bidirectional"))
      (node (ref "JP6") (pin "2") (pinfunction "2_2") (pintype "passive"))
    )
    (net (code "56") (name "/CS_VREF") (class "Default")
      (node (ref "C409") (pin "+") (pinfunction "+_+") (pintype "passive"))
      (node (ref "C410") (pin "1") (pinfunction "1_1") (pintype "passive"))
      (node (ref "IC2") (pin "3") (pinfunction "-IN_3") (pintype "input"))
      (node (ref "IC2") (pin "4") (pinfunction "OUT_4") (pintype "output"))
      (node (ref "IC4") (pin "16") (pinfunction "VQ2_16") (pintype "bidirectional"))
      (node (ref "IC4") (pin "19") (pinfunction "VQ3_19") (pintype "bidirectional"))
      (node (ref "JP6") (pin "5") (pinfunction "5_5") (pintype "passive"))
    )
    (net (code "57") (name "/CS_~{CS}") (class "Default")
      (node (ref "IC4") (pin "13") (pinfunction "AD0/~{CS}_13") (pintype "bidirectional"))
      (node (ref "IC8") (pin "69") (pinfunction "PB10_69") (pintype "bidirectional"))
    )
    (net (code "58") (name "/CS_~{RST}") (class "Default")
      (node (ref "IC4") (pin "14") (pinfunction "~{RST}_14") (pintype "bidirectional"))
      (node (ref "IC8") (pin "70") (pinfunction "PB11_70") (pintype "bidirectional"))
      (node (ref "R402") (pin "2") (pinfunction "2_2") (pintype "passive"))
    )
    (net (code "59") (name "/DRAM_A0") (class "Default")
      (node (ref "IC10") (pin "23") (pinfunction "A0_23") (pintype "bidirectional"))
      (node (ref "IC8") (pin "10") (pinfunction "PF0_10") (pintype "bidirectional"))
    )
    (net (code "60") (name "/DRAM_A1") (class "Default")
      (node (ref "IC10") (pin "24") (pinfunction "A1_24") (pintype "bidirectional"))
      (node (ref "IC8") (pin "11") (pinfunction "PF1_11") (pintype "bidirectional"))
    )
    (net (code "61") (name "/DRAM_A2") (class "Default")
      (node (ref "IC10") (pin "25") (pinfunction "A2_25") (pintype "bidirectional"))
      (node (ref "IC8") (pin "12") (pinfunction "PF2_12") (pintype "bidirectional"))
    )
    (net (code "62") (name "/DRAM_A3") (class "Default")
      (node (ref "IC10") (pin "26") (pinfunction "A3_26") (pintype "bidirectional"))
      (node (ref "IC8") (pin "13") (pinfunction "PF3_13") (pintype "bidirectional"))
    )
    (net (code "63") (name "/DRAM_A4") (class "Default")
      (node (ref "IC10") (pin "29") (pinfunction "A4_29") (pintype "bidirectional"))
      (node (ref "IC8") (pin "14") (pinfunction "PF4_14") (pintype "bidirectional"))
    )
    (net (code "64") (name "/DRAM_A5") (class "Default")
      (node (ref "IC10") (pin "30") (pinfunction "A5_30") (pintype "bidirectional"))
      (node (ref "IC8") (pin "15") (pinfunction "PF5_15") (pintype "bidirectional"))
    )
    (net (code "65") (name "/DRAM_A6") (class "Default")
      (node (ref "IC10") (pin "31") (pinfunction "A6_31") (pintype "bidirectional"))
      (node (ref "IC8") (pin "50") (pinfunction "PF12_50") (pintype "bidirectional"))
    )
    (net (code "66") (name "/DRAM_A7") (class "Default")
      (node (ref "IC10") (pin "32") (pinfunction "A7_32") (pintype "bidirectional"))
      (node (ref "IC8") (pin "53") (pinfunction "PF13_53") (pintype "bidirectional"))
    )
    (net (code "67") (name "/DRAM_A8") (class "Default")
      (node (ref "IC10") (pin "33") (pinfunction "A8_33") (pintype "bidirectional"))
      (node (ref "IC8") (pin "54") (pinfunction "PF14_54") (pintype "bidirectional"))
    )
    (net (code "68") (name "/DRAM_A9") (class "Default")
      (node (ref "IC10") (pin "34") (pinfunction "A9_34") (pintype "bidirectional"))
      (node (ref "IC8") (pin "55") (pinfunction "PF15_55") (pintype "bidirectional"))
    )
    (net (code "69") (name "/DRAM_A10") (class "Default")
      (node (ref "IC10") (pin "22") (pinfunction "A10_22") (pintype "bidirectional"))
      (node (ref "IC8") (pin "56") (pinfunction "PG0_56") (pintype "bidirectional"))
    )
    (net (code "70") (name "/DRAM_A11") (class "Default")
      (node (ref "IC10") (pin "35") (pinfunction "A11_35") (pintype "bidirectional"))
      (node (ref "IC8") (pin "57") (pinfunction "PG1_57") (pintype "bidirectional"))
    )
    (net (code "71") (name "/DRAM_BA0") (class "Default")
      (node (ref "IC10") (pin "20") (pinfunction "BA0_20") (pintype "bidirectional"))
      (node (ref "IC8") (pin "89") (pinfunction "PG4_89") (pintype "bidirectional"))
    )
    (net (code "72") (name "/DRAM_BA1") (class "Default")
      (node (ref "IC10") (pin "21") (pinfunction "BA1_21") (pintype "bidirectional"))
      (node (ref "IC8") (pin "90") (pinfunction "PG5_90") (pintype "bidirectional"))
    )
    (net (code "73") (name "/DRAM_CKE") (class "Default")
      (node (ref "IC10") (pin "37") (pinfunction "CKE_37") (pintype "bidirectional"))
      (node (ref "IC8") (pin "135") (pinfunction "PB5_135") (pintype "bidirectional"))
    )
    (net (code "74") (name "/DRAM_CLK") (class "Default")
      (node (ref "IC10") (pin "38") (pinfunction "CLK_38") (pintype "bidirectional"))
      (node (ref "IC8") (pin "93") (pinfunction "PG8_93") (pintype "bidirectional"))
    )
    (net (code "75") (name "/DRAM_DQ0") (class "Default")
      (node (ref "IC10") (pin "2") (pinfunction "DQ0_2") (pintype "bidirectional"))
      (node (ref "IC8") (pin "85") (pinfunction "PD14_85") (pintype "bidirectional"))
    )
    (net (code "76") (name "/DRAM_DQ1") (class "Default")
      (node (ref "IC10") (pin "4") (pinfunction "DQ1_4") (pintype "bidirectional"))
      (node (ref "IC8") (pin "86") (pinfunction "PD15_86") (pintype "bidirectional"))
    )
    (net (code "77") (name "/DRAM_DQ2") (class "Default")
      (node (ref "IC10") (pin "5") (pinfunction "DQ2_5") (pintype "bidirectional"))
      (node (ref "IC8") (pin "114") (pinfunction "PD0_114") (pintype "bidirectional"))
    )
    (net (code "78") (name "/DRAM_DQ3") (class "Default")
      (node (ref "IC10") (pin "7") (pinfunction "DQ3_7") (pintype "bidirectional"))
      (node (ref "IC8") (pin "115") (pinfunction "PD1_115") (pintype "bidirectional"))
    )
    (net (code "79") (name "/DRAM_DQ4") (class "Default")
      (node (ref "IC10") (pin "8") (pinfunction "DQ4_8") (pintype "bidirectional"))
      (node (ref "IC8") (pin "58") (pinfunction "PE7_58") (pintype "bidirectional"))
    )
    (net (code "80") (name "/DRAM_DQ5") (class "Default")
      (node (ref "IC10") (pin "10") (pinfunction "DQ5_10") (pintype "bidirectional"))
      (node (ref "IC8") (pin "59") (pinfunction "PE8_59") (pintype "bidirectional"))
    )
    (net (code "81") (name "/DRAM_DQ6") (class "Default")
      (node (ref "IC10") (pin "11") (pinfunction "DQ6_11") (pintype "bidirectional"))
      (node (ref "IC8") (pin "60") (pinfunction "PE9_60") (pintype "bidirectional"))
    )
    (net (code "82") (name "/DRAM_DQ7") (class "Default")
      (node (ref "IC10") (pin "13") (pinfunction "DQ7_13") (pintype "bidirectional"))
      (node (ref "IC8") (pin "63") (pinfunction "PE10_63") (pintype "bidirectional"))
    )
    (net (code "83") (name "/DRAM_DQ8") (class "Default")
      (node (ref "IC10") (pin "42") (pinfunction "DQ8_42") (pintype "bidirectional"))
      (node (ref "IC8") (pin "64") (pinfunction "PE11_64") (pintype "bidirectional"))
    )
    (net (code "84") (name "/DRAM_DQ9") (class "Default")
      (node (ref "IC10") (pin "44") (pinfunction "DQ9_44") (pintype "bidirectional"))
      (node (ref "IC8") (pin "65") (pinfunction "PE12_65") (pintype "bidirectional"))
    )
    (net (code "85") (name "/DRAM_DQ10") (class "Default")
      (node (ref "IC10") (pin "45") (pinfunction "DQ10_45") (pintype "bidirectional"))
      (node (ref "IC8") (pin "66") (pinfunction "PE13_66") (pintype "bidirectional"))
    )
    (net (code "86") (name "/DRAM_DQ11") (class "Default")
      (node (ref "IC10") (pin "47") (pinfunction "DQ11_47") (pintype "bidirectional"))
      (node (ref "IC8") (pin "67") (pinfunction "PE14_67") (pintype "bidirectional"))
    )
    (net (code "87") (name "/DRAM_DQ12") (class "Default")
      (node (ref "IC10") (pin "48") (pinfunction "DQ12_48") (pintype "bidirectional"))
      (node (ref "IC8") (pin "68") (pinfunction "PE15_68") (pintype "bidirectional"))
    )
    (net (code "88") (name "/DRAM_DQ13") (class "Default")
      (node (ref "IC10") (pin "50") (pinfunction "DQ13_50") (pintype "bidirectional"))
      (node (ref "IC8") (pin "77") (pinfunction "PD8_77") (pintype "bidirectional"))
    )
    (net (code "89") (name "/DRAM_DQ14") (class "Default")
      (node (ref "IC10") (pin "51") (pinfunction "DQ14_51") (pintype "bidirectional"))
      (node (ref "IC8") (pin "78") (pinfunction "PD9_78") (pintype "bidirectional"))
    )
    (net (code "90") (name "/DRAM_DQ15") (class "Default")
      (node (ref "IC10") (pin "53") (pinfunction "DQ15_53") (pintype "bidirectional"))
      (node (ref "IC8") (pin "79") (pinfunction "PD10_79") (pintype "bidirectional"))
    )
    (net (code "91") (name "/DRAM_LDQM") (class "Default")
      (node (ref "IC10") (pin "15") (pinfunction "LDQM_15") (pintype "bidirectional"))
      (node (ref "IC8") (pin "141") (pinfunction "PE0_141") (pintype "bidirectional"))
    )
    (net (code "92") (name "/DRAM_UDQM") (class "Default")
      (node (ref "IC10") (pin "39") (pinfunction "UDQM_39") (pintype "bidirectional"))
      (node (ref "IC8") (pin "142") (pinfunction "PE1_142") (pintype "bidirectional"))
    )
    (net (code "93") (name "/DRAM_~{CAS}") (class "Default")
      (node (ref "IC10") (pin "17") (pinfunction "~{CAS}_17") (pintype "bidirectional"))
      (node (ref "IC8") (pin "132") (pinfunction "PG15_132") (pintype "bidirectional"))
    )
    (net (code "94") (name "/DRAM_~{CS}") (class "Default")
      (node (ref "IC10") (pin "19") (pinfunction "~{CS}_19") (pintype "bidirectional"))
      (node (ref "IC8") (pin "136") (pinfunction "PB6_136") (pintype "bidirectional"))
    )
    (net (code "95") (name "/DRAM_~{RAS}") (class "Default")
      (node (ref "IC10") (pin "18") (pinfunction "~{RAS}_18") (pintype "bidirectional"))
      (node (ref "IC8") (pin "49") (pinfunction "PF11_49") (pintype "bidirectional"))
    )
    (net (code "96") (name "/DRAM_~{WE}") (class "Default")
      (node (ref "IC10") (pin "16") (pinfunction "~{WE}_16") (pintype "bidirectional"))
      (node (ref "IC8") (pin "26") (pinfunction "PC0_26") (pintype "bidirectional"))
    )
    (net (code "97") (name "/FLASH_CLK") (class "Default")
      (node (ref "IC8") (pin "133") (pinfunction "PB3_133") (pintype "bidirectional"))
      (node (ref "IC9") (pin "6") (pinfunction "C_6") (pintype "bidirectional"))
    )
    (net (code "98") (name "/FLASH_HOLD") (class "Default")
      (node (ref "IC8") (pin "44") (pinfunction "PC4_44") (pintype "bidirectional"))
      (node (ref "IC9") (pin "7") (pinfunction "HOLD#/DQ3_7") (pintype "bidirectional"))
    )
    (net (code "99") (name "/FLASH_MISO") (class "Default")
      (node (ref "IC8") (pin "42") (pinfunction "PA6_42") (pintype "bidirectional"))
      (node (ref "IC9") (pin "2") (pinfunction "DQ1_2") (pintype "bidirectional"))
    )
    (net (code "100") (name "/FLASH_MOSI") (class "Default")
      (node (ref "IC8") (pin "43") (pinfunction "PA7_43") (pintype "bidirectional"))
      (node (ref "IC9") (pin "5") (pinfunction "DQ0_5") (pintype "bidirectional"))
    )
    (net (code "101") (name "/FLASH_NCS") (class "Default")
      (node (ref "IC8") (pin "45") (pinfunction "PC5_45") (pintype "bidirectional"))
      (node (ref "IC9") (pin "1") (pinfunction "S#_1") (pintype "bidirectional"))
      (node (ref "R901") (pin "2") (pinfunction "2_2") (pintype "passive"))
    )
    (net (code "102") (name "/FLASH_W") (class "Default")
      (node (ref "IC8") (pin "46") (pinfunction "PB0_46") (pintype "bidirectional"))
      (node (ref "IC9") (pin "3") (pinfunction "VPP/W#/DQ2_3") (pintype "bidirectional"))
    )
    (net (code "103") (name "/NRST") (class "Default")
      (node (ref "C15") (pin "1") (pinfunction "1_1") (pintype "passive"))
      (node (ref "IC8") (pin "25") (pinfunction "NRST_25") (pintype "bidirectional"))
      (node (ref "JP4") (pin "5") (pinfunction "5_5") (pintype "passive"))
      (node (ref "X2") (pin "5") (pinfunction "S_5") (pintype "passive"))
    )
    (net (code "104") (name "/SWCLK") (class "Default")
      (node (ref "IC8") (pin "109") (pinfunction "PA14_109") (pintype "bidirectional"))
      (node (ref "JP4") (pin "2") (pinfunction "2_2") (pintype "passive"))
      (node (ref "X2") (pin "2") (pinfunction "S_2") (pintype "passive"))
    )
    (net (code "105") (name "/SWDIO") (class "Default")
      (node (ref "IC8") (pin "105") (pinfunction "PA13_105") (pintype "bidirectional"))
      (node (ref "JP4") (pin "4") (pinfunction "4_4") (pintype "passive"))
      (node (ref "X2") (pin "4") (pinfunction "S_4") (pintype "passive"))
    )
    (net (code "106") (name "/USBD_DM") (class "Default")
      (node (ref "IC8") (pin "103") (pinfunction "PA11_103") (pintype "bidirectional"))
      (node (ref "JP7") (pin "3") (pinfunction "3_3") (pintype "passive"))
      (node (ref "R1") (pin "2") (pinfunction "2_2") (pintype "passive"))
    )
    (net (code "107") (name "/USBD_DP") (class "Default")
      (node (ref "IC8") (pin "104") (pinfunction "PA12_104") (pintype "bidirectional"))
      (node (ref "JP7") (pin "2") (pinfunction "2_2") (pintype "passive"))
      (node (ref "R2") (pin "2") (pinfunction "2_2") (pintype "passive"))
    )
    (net (code "108") (name "/USBD_ID") (class "Default")
      (node (ref "IC8") (pin "102") (pinfunction "PA10_102") (pintype "bidirectional"))
      (node (ref "JP7") (pin "1") (pinfunction "1_1") (pintype "passive"))
      (node (ref "USB") (pin "4") (pinfunction "ID_4") (pintype "bidirectional"))
    )
    (net (code "109") (name "/USBD_VBUS") (class "Default")
      (node (ref "IC8") (pin "101") (pinfunction "PA9_101") (pintype "bidirectional"))
      (node (ref "JP7") (pin "4") (pinfunction "4_4") (pintype "passive"))
      (node (ref "L1") (pin "1") (pinfunction "1_1") (pintype "passive"))
    )
    (net (code "110") (name "/USBH_DM") (class "Default")
      (node (ref "IC8") (pin "75") (pinfunction "PB14_75") (pintype "bidirectional"))
      (node (ref "JP11") (pin "1") (pinfunction "1_1") (pintype "passive"))
    )
    (net (code "111") (name "/USBH_DP") (class "Default")
      (node (ref "IC8") (pin "76") (pinfunction "PB15_76") (pintype "bidirectional"))
      (node (ref "JP11") (pin "2") (pinfunction "2_2") (pintype "passive"))
    )
    (net (code "112") (name "/USBH_ID") (class "Default")
      (node (ref "IC8") (pin "73") (pinfunction "PB12_73") (pintype "bidirectional"))
      (node (ref "JP11") (pin "3") (pinfunction "3_3") (pintype "passive"))
    )
    (net (code "113") (name "/USBH_VBUS") (class "Default")
      (node (ref "IC8") (pin "74") (pinfunction "PB13_74") (pintype "bidirectional"))
      (node (ref "JP11") (pin "4") (pinfunction "4_4") (pintype "passive"))
    )
    (net (code "114") (name "/VBAT") (class "Default")
      (node (ref "IC8") (pin "6") (pinfunction "VBAT_6") (pintype "bidirectional"))
      (node (ref "JP15") (pin "1") (pinfunction "1_1") (pintype "passive"))
    )
    (net (code "115") (name "/VDDA") (class "Default")
      (node (ref "C24") (pin "1") (pinfunction "1_1") (pintype "passive"))
      (node (ref "C27") (pin "1") (pinfunction "1_1") (pintype "passive"))
      (node (ref "IC8") (pin "33") (pinfunction "VDDA_33") (pintype "bidirectional"))
      (node (ref "L4") (pin "1") (pinfunction "1_1") (pintype "passive"))
    )
    (net (code "116") (name "GND") (class "Default")
      (node (ref "C1") (pin "2") (pinfunction "2_2") (pintype "passive"))
      (node (ref "C10") (pin "2") (pinfunction "2_2") (pintype "passive"))
      (node (ref "C11") (pin "2") (pinfunction "2_2") (pintype "passive"))
      (node (ref "C110") (pin "1") (pinfunction "1_1") (pintype "passive"))
      (node (ref "C111") (pin "-") (pinfunction "-_-") (pintype "passive"))
      (node (ref "C112") (pin "2") (pinfunction "2_2") (pintype "passive"))
      (node (ref "C12") (pin "2") (pinfunction "2_2") (pintype "passive"))
      (node (ref "C15") (pin "2") (pinfunction "2_2") (pintype "passive"))
      (node (ref "C17") (pin "2") (pinfunction "2_2") (pintype "passive"))
      (node (ref "C18") (pin "2") (pinfunction "2_2") (pintype "passive"))
      (node (ref "C19") (pin "2") (pinfunction "2_2") (pintype "passive"))
      (node (ref "C2") (pin "2") (pinfunction "2_2") (pintype "passive"))
      (node (ref "C20") (pin "2") (pinfunction "2_2") (pintype "passive"))
      (node (ref "C24") (pin "2") (pinfunction "2_2") (pintype "passive"))
      (node (ref "C27") (pin "2") (pinfunction "2_2") (pintype "passive"))
      (node (ref "C3") (pin "2") (pinfunction "2_2") (pintype "passive"))
      (node (ref "C33") (pin "2") (pinfunction "2_2") (pintype "passive"))
      (node (ref "C34") (pin "2") (pinfunction "2_2") (pintype "passive"))
      (node (ref "C35") (pin "2") (pinfunction "2_2") (pintype "passive"))
      (node (ref "C37") (pin "2") (pinfunction "2_2") (pintype "passive"))
      (node (ref "C38") (pin "2") (pinfunction "2_2") (pintype "passive"))
      (node (ref "C39") (pin "2") (pinfunction "2_2") (pintype "passive"))
      (node (ref "C4") (pin "-") (pinfunction "-_-") (pintype "passive"))
      (node (ref "C40") (pin "2") (pinfunction "2_2") (pintype "passive"))
      (node (ref "C401") (pin "2") (pinfunction "2_2") (pintype "passive"))
      (node (ref "C402") (pin "2") (pinfunction "2_2") (pintype "passive"))
      (node (ref "C403") (pin "2") (pinfunction "2_2") (pintype "passive"))
      (node (ref "C404") (pin "2") (pinfunction "2_2") (pintype "passive"))
      (node (ref "C405") (pin "2") (pinfunction "2_2") (pintype "passive"))
      (node (ref "C406") (pin "2") (pinfunction "2_2") (pintype "passive"))
      (node (ref "C407") (pin "2") (pinfunction "2_2") (pintype "passive"))
      (node (ref "C408") (pin "2") (pinfunction "2_2") (pintype "passive"))
      (node (ref "C409") (pin "-") (pinfunction "-_-") (pintype "passive"))
      (node (ref "C41") (pin "2") (pinfunction "2_2") (pintype "passive"))
      (node (ref "C410") (pin "2") (pinfunction "2_2") (pintype "passive"))
      (node (ref "C411") (pin "2") (pinfunction "2_2") (pintype "passive"))
      (node (ref "C412") (pin "-") (pinfunction "-_-") (pintype "passive"))
      (node (ref "C42") (pin "2") (pinfunction "2_2") (pintype "passive"))
      (node (ref "C43") (pin "2") (pinfunction "2_2") (pintype "passive"))
      (node (ref "C5") (pin "2") (pinfunction "2_2") (pintype "passive"))
      (node (ref "C6") (pin "2") (pinfunction "2_2") (pintype "passive"))
      (node (ref "C7") (pin "2") (pinfunction "2_2") (pintype "passive"))
      (node (ref "C8") (pin "2") (pinfunction "2_2") (pintype "passive"))
      (node (ref "C9") (pin "2") (pinfunction "2_2") (pintype "passive"))
      (node (ref "C901") (pin "2") (pinfunction "2_2") (pintype "passive"))
      (node (ref "IC10") (pin "12") (pinfunction "GNDQ1_12") (pintype "bidirectional"))
      (node (ref "IC10") (pin "28") (pinfunction "GND1_28") (pintype "bidirectional"))
      (node (ref "IC10") (pin "41") (pinfunction "GND_41") (pintype "bidirectional"))
      (node (ref "IC10") (pin "46") (pinfunction "GNDQ2_46") (pintype "bidirectional"))
      (node (ref "IC10") (pin "52") (pinfunction "GNDQ3_52") (pintype "bidirectional"))
      (node (ref "IC10") (pin "54") (pinfunction "GND2_54") (pintype "bidirectional"))
      (node (ref "IC10") (pin "6") (pinfunction "GNDQ_6") (pintype "bidirectional"))
      (node (ref "IC2") (pin "2") (pinfunction "V-_2") (pintype "power_in"))
      (node (ref "IC4") (pin "21") (pinfunction "AGND_21") (pintype "bidirectional"))
      (node (ref "IC4") (pin "8") (pinfunction "DGND_8") (pintype "bidirectional"))
      (node (ref "IC8") (pin "107") (pinfunction "VSS6_107") (pintype "bidirectional"))
      (node (ref "IC8") (pin "120") (pinfunction "VSS7_120") (pintype "bidirectional"))
      (node (ref "IC8") (pin "130") (pinfunction "VSS8_130") (pintype "bidirectional"))
      (node (ref "IC8") (pin "143") (pinfunction "PDR_ON_143") (pintype "bidirectional"))
      (node (ref "IC8") (pin "16") (pinfunction "VSS_16") (pintype "bidirectional"))
      (node (ref "IC8") (pin "31") (pinfunction "VSSA_31") (pintype "bidirectional"))
      (node (ref "IC8") (pin "38") (pinfunction "VSS1_38") (pintype "bidirectional"))
      (node (ref "IC8") (pin "51") (pinfunction "VSS2_51") (pintype "bidirectional"))
      (node (ref "IC8") (pin "61") (pinfunction "VSS3_61") (pintype "bidirectional"))
      (node (ref "IC8") (pin "83") (pinfunction "VSS4_83") (pintype "bidirectional"))
      (node (ref "IC8") (pin "94") (pinfunction "VSS5_94") (pintype "bidirectional"))
      (node (ref "IC9") (pin "4") (pinfunction "VSS_4") (pintype "bidirectional"))
      (node (ref "JP2") (pin "2") (pinfunction "2_2") (pintype "passive"))
      (node (ref "JP4") (pin "3") (pinfunction "3_3") (pintype "passive"))
      (node (ref "JP5") (pin "2") (pinfunction "2_2") (pintype "passive"))
      (node (ref "JP6") (pin "6") (pinfunction "6_6") (pintype "passive"))
      (node (ref "JP7") (pin "5") (pinfunction "5_5") (pintype "passive"))
      (node (ref "L2") (pin "2") (pinfunction "2_2") (pintype "passive"))
      (node (ref "R3") (pin "1") (pinfunction "1_1") (pintype "passive"))
      (node (ref "R402") (pin "1") (pinfunction "1_1") (pintype "passive"))
      (node (ref "U4") (pin "2") (pinfunction "GND_2") (pintype "input"))
      (node (ref "X2") (pin "3") (pinfunction "S_3") (pintype "passive"))
    )
    (net (code "117") (name "Net-(IC4-FILT+)") (class "Default")
      (node (ref "C411") (pin "1") (pinfunction "1_1") (pintype "passive"))
      (node (ref "C412") (pin "+") (pinfunction "+_+") (pintype "passive"))
      (node (ref "IC4") (pin "22") (pinfunction "FILT+_22") (pintype "bidirectional"))
    )
    (net (code "118") (name "Net-(IC4-VA)") (class "Default")
      (node (ref "C407") (pin "1") (pinfunction "1_1") (pintype "passive"))
      (node (ref "C408") (pin "1") (pinfunction "1_1") (pintype "passive"))
      (node (ref "IC4") (pin "20") (pinfunction "VA_20") (pintype "bidirectional"))
      (node (ref "L3") (pin "2") (pinfunction "2_2") (pintype "passive"))
    )
    (net (code "119") (name "Net-(IC4-VD)") (class "Default")
      (node (ref "C405") (pin "1") (pinfunction "1_1") (pintype "passive"))
      (node (ref "C406") (pin "1") (pinfunction "1_1") (pintype "passive"))
      (node (ref "IC4") (pin "9") (pinfunction "VD_9") (pintype "bidirectional"))
      (node (ref "R401") (pin "1") (pinfunction "1_1") (pintype "passive"))
    )
    (net (code "120") (name "Net-(IC4-XTI)") (class "Default")
      (node (ref "C401") (pin "1") (pinfunction "1_1") (pintype "passive"))
      (node (ref "IC4") (pin "2") (pinfunction "XTI_2") (pintype "bidirectional"))
      (node (ref "Y1") (pin "2") (pinfunction "2_2") (pintype "passive"))
    )
    (net (code "121") (name "Net-(IC4-XTO)") (class "Default")
      (node (ref "C402") (pin "1") (pinfunction "1_1") (pintype "passive"))
      (node (ref "IC4") (pin "1") (pinfunction "XTO_1") (pintype "bidirectional"))
      (node (ref "Y1") (pin "1") (pinfunction "1_1") (pintype "passive"))
    )
    (net (code "122") (name "Net-(IC8A-PH0)") (class "Default")
      (node (ref "C11") (pin "1") (pinfunction "1_1") (pintype "passive"))
      (node (ref "IC8") (pin "23") (pinfunction "PH0_23") (pintype "bidirectional"))
      (node (ref "Y3") (pin "2") (pinfunction "2_2") (pintype "passive"))
    )
    (net (code "123") (name "Net-(IC8A-PH1)") (class "Default")
      (node (ref "C12") (pin "1") (pinfunction "1_1") (pintype "passive"))
      (node (ref "IC8") (pin "24") (pinfunction "PH1_24") (pintype "bidirectional"))
      (node (ref "Y3") (pin "1") (pinfunction "1_1") (pintype "passive"))
    )
    (net (code "124") (name "Net-(IC8B-VCAP_1)") (class "Default")
      (node (ref "C20") (pin "1") (pinfunction "1_1") (pintype "passive"))
      (node (ref "IC8") (pin "71") (pinfunction "VCAP_1_71") (pintype "bidirectional"))
    )
    (net (code "125") (name "Net-(IC8C-VCAP_2)") (class "Default")
      (node (ref "C19") (pin "1") (pinfunction "1_1") (pintype "passive"))
      (node (ref "IC8") (pin "106") (pinfunction "VCAP_2_106") (pintype "bidirectional"))
    )
    (net (code "126") (name "Net-(USB-D+)") (class "Default")
      (node (ref "R2") (pin "1") (pinfunction "1_1") (pintype "passive"))
      (node (ref "USB") (pin "3") (pinfunction "D+_3") (pintype "bidirectional"))
    )
    (net (code "127") (name "Net-(USB-D-)") (class "Default")
      (node (ref "R1") (pin "1") (pinfunction "1_1") (pintype "passive"))
      (node (ref "USB") (pin "2") (pinfunction "D-_2") (pintype "bidirectional"))
    )
    (net (code "128") (name "Net-(USB-GND)") (class "Default")
      (node (ref "L2") (pin "1") (pinfunction "1_1") (pintype "passive"))
      (node (ref "USB") (pin "5") (pinfunction "GND_5") (pintype "bidirectional"))
      (node (ref "USB") (pin "G") (pinfunction "SHIELD_G") (pintype "bidirectional"))
      (node (ref "USB") (pin "G2") (pinfunction "SHIELD_G2") (pintype "bidirectional"))
      (node (ref "USB") (pin "G3") (pinfunction "SHIELD_G3") (pintype "bidirectional"))
      (node (ref "USB") (pin "G4") (pinfunction "SHIELD_G4") (pintype "bidirectional"))
    )
    (net (code "129") (name "Net-(USB-VCC)") (class "Default")
      (node (ref "L1") (pin "2") (pinfunction "2_2") (pintype "passive"))
      (node (ref "USB") (pin "1") (pinfunction "VCC_1") (pintype "bidirectional"))
    )
    (net (code "130") (name "unconnected-(IC4-MCLK-Pad3)") (class "Default")
      (node (ref "IC4") (pin "3") (pinfunction "MCLK_3") (pintype "bidirectional"))
    )
    (net (code "131") (name "unconnected-(IC4-~{AMUTEC}-Pad23)") (class "Default")
      (node (ref "IC4") (pin "23") (pinfunction "~{AMUTEC}_23") (pintype "bidirectional"))
    )
    (net (code "132") (name "unconnected-(IC4-~{BMUTEC}-Pad28)") (class "Default")
      (node (ref "IC4") (pin "28") (pinfunction "~{BMUTEC}_28") (pintype "bidirectional"))
    )
    (net (code "133") (name "unconnected-(IC8A-PC15-Pad9)") (class "Default")
      (node (ref "IC8") (pin "9") (pinfunction "PC15_9") (pintype "bidirectional"))
    )
    (net (code "134") (name "unconnected-(IC8A-PF6-Pad18)") (class "Default")
      (node (ref "IC8") (pin "18") (pinfunction "PF6_18") (pintype "bidirectional"))
    )
    (net (code "135") (name "unconnected-(IC8B-PG2-Pad87)") (class "Default")
      (node (ref "IC8") (pin "87") (pinfunction "PG2_87") (pintype "bidirectional"))
    )
    (net (code "136") (name "unconnected-(IC8B-PG3-Pad88)") (class "Default")
      (node (ref "IC8") (pin "88") (pinfunction "PG3_88") (pintype "bidirectional"))
    )
    (net (code "137") (name "unconnected-(IC8B-PG6-Pad91)") (class "Default")
      (node (ref "IC8") (pin "91") (pinfunction "PG6_91") (pintype "bidirectional"))
    )
    (net (code "138") (name "unconnected-(IC8B-PG7-Pad92)") (class "Default")
      (node (ref "IC8") (pin "92") (pinfunction "PG7_92") (pintype "bidirectional"))
    )
    (net (code "139") (name "unconnected-(IC8C-PC7-Pad97)") (class "Default")
      (node (ref "IC8") (pin "97") (pinfunction "PC7_97") (pintype "bidirectional"))
    )
    (net (code "140") (name "unconnected-(IC8C-PD3-Pad117)") (class "Default")
      (node (ref "IC8") (pin "117") (pinfunction "PD3_117") (pintype "bidirectional"))
    )
    (net (code "141") (name "unconnected-(IC8C-PD4-Pad118)") (class "Default")
      (node (ref "IC8") (pin "118") (pinfunction "PD4_118") (pintype "bidirectional"))
    )
    (net (code "142") (name "unconnected-(IC8C-PD5-Pad119)") (class "Default")
      (node (ref "IC8") (pin "119") (pinfunction "PD5_119") (pintype "bidirectional"))
    )
    (net (code "143") (name "unconnected-(IC8C-PG10-Pad125)") (class "Default")
      (node (ref "IC8") (pin "125") (pinfunction "PG10_125") (pintype "bidirectional"))
    )
  )
)
